# ethernet.net
KiCad netlist of a schematic drawn in Altium Designer
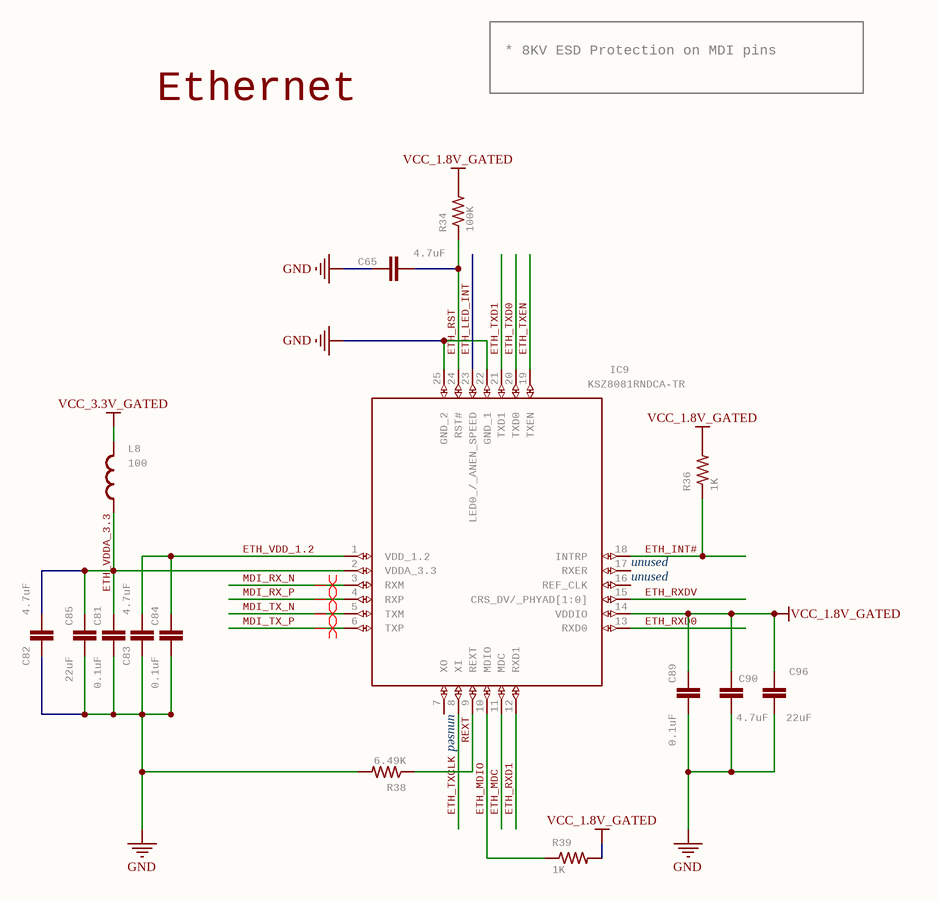
[diagram p0: ethernet.SchDoc]

(export (version "E")
  (design (tool "Eeschema 10.0.6"))
  (components
    (comp (ref "C65")
      (value "4.7uF")
      (footprint "0402-CAP")
      (description "CapacitorStandard 0603 ceramic capacitor, and 0.1\" leaded capacitor.")
      (fields (field (name "MPN") "JMK105BBJ475MV-F") (field (name "LIBRARYNAME") "sfe"))
      (libsource (lib "") (part "CAP0402-CAP_1"))
    )
    (comp (ref "C81")
      (value "0.1uF")
      (footprint "0402-CAP")
      (description "CAPACITOR, European symbol")
      (fields (field (name "MPN") "C0402C104Z4VAC"))
      (libsource (lib "openmv-ae3") (part "C-EUC0201"))
    )
    (comp (ref "C82")
      (value "4.7uF")
      (footprint "0402-CAP")
      (description "CapacitorStandard 0603 ceramic capacitor, and 0.1\" leaded capacitor.")
      (fields (field (name "MPN") "JMK105BBJ475MV-F") (field (name "LIBRARYNAME") "sfe"))
      (libsource (lib "openmv-ae3") (part "CAP0402-CAP"))
    )
    (comp (ref "C83")
      (value "4.7uF")
      (footprint "0402-CAP")
      (description "CapacitorStandard 0603 ceramic capacitor, and 0.1\" leaded capacitor.")
      (fields (field (name "MPN") "JMK105BBJ475MV-F") (field (name "LIBRARYNAME") "sfe"))
      (libsource (lib "openmv-ae3") (part "CAP0402-CAP"))
    )
    (comp (ref "C84")
      (value "0.1uF")
      (footprint "0402-CAP")
      (description "CAPACITOR, European symbol")
      (fields (field (name "MPN") "C0402C104Z4VAC"))
      (libsource (lib "openmv-ae3") (part "C-EUC0201"))
    )
    (comp (ref "C85")
      (value "22uF")
      (footprint "0805")
      (fields (field (name "MPN") "CL21A226MQQNNNE"))
      (libsource (lib "openmv-ae3") (part "22UF-0805-6.3V-20%"))
    )
    (comp (ref "C89")
      (value "0.1uF")
      (footprint "0402-CAP")
      (description "CAPACITOR, European symbol")
      (fields (field (name "MPN") "C0402C104Z4VAC"))
      (libsource (lib "openmv-ae3") (part "C-EUC0201"))
    )
    (comp (ref "C90")
      (value "4.7uF")
      (footprint "0402-CAP")
      (description "CapacitorStandard 0603 ceramic capacitor, and 0.1\" leaded capacitor.")
      (fields (field (name "MPN") "JMK105BBJ475MV-F") (field (name "LIBRARYNAME") "sfe"))
      (libsource (lib "openmv-ae3") (part "CAP0402-CAP"))
    )
    (comp (ref "C96")
      (value "22uF")
      (footprint "0805")
      (fields (field (name "MPN") "CL21A226MQQNNNE"))
      (libsource (lib "openmv-ae3") (part "22UF-0805-6.3V-20%"))
    )
    (comp (ref "IC9")
      (value "KSZ8081RNDCA-TR")
      (footprint "QFN50P400X400X90-25N")
      (description "Ethernet ICs 10/100 BASE-TX Physical Layer Transceiver   Source:  Datasheet")
      (fields (field (name "MOUSER_PART_NUMBER") "998-KSZ8081RNDCATR"))
      (libsource (lib "openmv-ae3") (part "KSZ8081RNDCA-TR"))
    )
    (comp (ref "L8")
      (value "100")
      (footprint "C0402")
      (fields (field (name "MPN") "MFBM1V1005-101-R") (field (name "LIBRARYNAME") "sfe"))
      (libsource (lib "openmv-ae3") (part "INDUCTOR0402"))
    )
    (comp (ref "R34")
      (value "100K")
      (footprint "0402-RES")
      (description "ResistorBasic schematic elements and footprints for 0603, 1206, and PTH resistors.")
      (fields (field (name "MPN") "AC0402FR-07100KL") (field (name "LIBRARYNAME") "sfe"))
      (libsource (lib "openmv-ae3") (part "RESISTOR0402-RES"))
    )
    (comp (ref "R36")
      (value "1K")
      (footprint "0402-RES")
      (description "ResistorBasic schematic elements and footprints for 0603, 1206, and PTH resistors.")
      (fields (field (name "MPN") "CRCW04021K00FKEDC") (field (name "LIBRARYNAME") "sfe"))
      (libsource (lib "openmv-ae3") (part "RESISTOR0402-RES"))
    )
    (comp (ref "R38")
      (value "6.49K")
      (footprint "0402-RES")
      (description "ResistorBasic schematic elements and footprints for 0603, 1206, and PTH resistors.")
      (fields (field (name "MPN") "CR0402-FX-6491GLF") (field (name "LIBRARYNAME") "sfe"))
      (libsource (lib "openmv-ae3") (part "RESISTOR0402-RES"))
    )
    (comp (ref "R39")
      (value "1K")
      (footprint "0402-RES")
      (description "ResistorBasic schematic elements and footprints for 0603, 1206, and PTH resistors.")
      (fields (field (name "MPN") "CRCW04021K00FKEDC") (field (name "LIBRARYNAME") "sfe"))
      (libsource (lib "openmv-ae3") (part "RESISTOR0402-RES"))
    )
  )
  (nets
    (net (code "1") (name "/ETH_INT#") (class "Default")
      (node (ref "IC9") (pin "18") (pinfunction "INTRP_18") (pintype "bidirectional"))
      (node (ref "R36") (pin "1") (pinfunction "1_1") (pintype "passive"))
    )
    (net (code "2") (name "/ETH_LED_INT") (class "Default")
      (node (ref "IC9") (pin "23") (pinfunction "LED0_/_ANEN_SPEED_23") (pintype "bidirectional"))
    )
    (net (code "3") (name "/ETH_MDC") (class "Default")
      (node (ref "IC9") (pin "11") (pinfunction "MDC_11") (pintype "bidirectional"))
    )
    (net (code "4") (name "/ETH_MDIO") (class "Default")
      (node (ref "IC9") (pin "10") (pinfunction "MDIO_10") (pintype "bidirectional"))
      (node (ref "R39") (pin "1") (pinfunction "1_1") (pintype "passive"))
    )
    (net (code "5") (name "/ETH_RST") (class "Default")
      (node (ref "C65") (pin "2") (pinfunction "2_2") (pintype "passive"))
      (node (ref "IC9") (pin "24") (pinfunction "RST#_24") (pintype "bidirectional"))
      (node (ref "R34") (pin "1") (pinfunction "1_1") (pintype "passive"))
    )
    (net (code "6") (name "/ETH_RXD0") (class "Default")
      (node (ref "IC9") (pin "13") (pinfunction "RXD0_13") (pintype "bidirectional"))
    )
    (net (code "7") (name "/ETH_RXD1") (class "Default")
      (node (ref "IC9") (pin "12") (pinfunction "RXD1_12") (pintype "bidirectional"))
    )
    (net (code "8") (name "/ETH_RXDV") (class "Default")
      (node (ref "IC9") (pin "15") (pinfunction "CRS_DV/_PHYAD[1:0]_15") (pintype "bidirectional"))
    )
    (net (code "9") (name "/ETH_TXCLK") (class "Default")
      (node (ref "IC9") (pin "8") (pinfunction "XI_8") (pintype "bidirectional"))
    )
    (net (code "10") (name "/ETH_TXD0") (class "Default")
      (node (ref "IC9") (pin "20") (pinfunction "TXD0_20") (pintype "bidirectional"))
    )
    (net (code "11") (name "/ETH_TXD1") (class "Default")
      (node (ref "IC9") (pin "21") (pinfunction "TXD1_21") (pintype "bidirectional"))
    )
    (net (code "12") (name "/ETH_TXEN") (class "Default")
      (node (ref "IC9") (pin "19") (pinfunction "TXEN_19") (pintype "bidirectional"))
    )
    (net (code "13") (name "/ETH_VDDA_3.3") (class "Default")
      (node (ref "C81") (pin "1") (pinfunction "1_1") (pintype "passive"))
      (node (ref "C82") (pin "2") (pinfunction "2_2") (pintype "passive"))
      (node (ref "C85") (pin "1") (pinfunction "1_1") (pintype "passive"))
      (node (ref "IC9") (pin "2") (pinfunction "VDDA_3.3_2") (pintype "bidirectional"))
      (node (ref "L8") (pin "1") (pinfunction "1_1") (pintype "passive"))
    )
    (net (code "14") (name "/ETH_VDD_1.2") (class "Default")
      (node (ref "C83") (pin "2") (pinfunction "2_2") (pintype "passive"))
      (node (ref "C84") (pin "1") (pinfunction "1_1") (pintype "passive"))
      (node (ref "IC9") (pin "1") (pinfunction "VDD_1.2_1") (pintype "bidirectional"))
    )
    (net (code "15") (name "/MDI_RX_N") (class "Default")
      (node (ref "IC9") (pin "3") (pinfunction "RXM_3") (pintype "bidirectional"))
    )
    (net (code "16") (name "/MDI_RX_P") (class "Default")
      (node (ref "IC9") (pin "4") (pinfunction "RXP_4") (pintype "bidirectional"))
    )
    (net (code "17") (name "/MDI_TX_N") (class "Default")
      (node (ref "IC9") (pin "5") (pinfunction "TXM_5") (pintype "bidirectional"))
    )
    (net (code "18") (name "/MDI_TX_P") (class "Default")
      (node (ref "IC9") (pin "6") (pinfunction "TXP_6") (pintype "bidirectional"))
    )
    (net (code "19") (name "/REXT") (class "Default")
      (node (ref "IC9") (pin "9") (pinfunction "REXT_9") (pintype "bidirectional"))
      (node (ref "R38") (pin "1") (pinfunction "1_1") (pintype "passive"))
    )
    (net (code "20") (name "GND") (class "Default")
      (node (ref "C65") (pin "1") (pinfunction "1_1") (pintype "passive"))
      (node (ref "C81") (pin "2") (pinfunction "2_2") (pintype "passive"))
      (node (ref "C82") (pin "1") (pinfunction "1_1") (pintype "passive"))
      (node (ref "C83") (pin "1") (pinfunction "1_1") (pintype "passive"))
      (node (ref "C84") (pin "2") (pinfunction "2_2") (pintype "passive"))
      (node (ref "C85") (pin "2") (pinfunction "2_2") (pintype "passive"))
      (node (ref "C89") (pin "2") (pinfunction "2_2") (pintype "passive"))
      (node (ref "C90") (pin "1") (pinfunction "1_1") (pintype "passive"))
      (node (ref "C96") (pin "2") (pinfunction "2_2") (pintype "passive"))
      (node (ref "IC9") (pin "22") (pinfunction "GND_1_22") (pintype "bidirectional"))
      (node (ref "IC9") (pin "25") (pinfunction "GND_2_25") (pintype "bidirectional"))
      (node (ref "R38") (pin "2") (pinfunction "2_2") (pintype "passive"))
    )
    (net (code "21") (name "VCC_1.8V_GATED") (class "Default")
      (node (ref "C89") (pin "1") (pinfunction "1_1") (pintype "passive"))
      (node (ref "C90") (pin "2") (pinfunction "2_2") (pintype "passive"))
      (node (ref "C96") (pin "1") (pinfunction "1_1") (pintype "passive"))
      (node (ref "IC9") (pin "14") (pinfunction "VDDIO_14") (pintype "bidirectional"))
      (node (ref "R34") (pin "2") (pinfunction "2_2") (pintype "passive"))
      (node (ref "R36") (pin "2") (pinfunction "2_2") (pintype "passive"))
      (node (ref "R39") (pin "2") (pinfunction "2_2") (pintype "passive"))
    )
    (net (code "22") (name "VCC_3.3V_GATED") (class "Default")
      (node (ref "L8") (pin "2") (pinfunction "2_2") (pintype "passive"))
    )
    (net (code "23") (name "unconnected-(IC9-REF_CLK-Pad16)") (class "Default")
      (node (ref "IC9") (pin "16") (pinfunction "REF_CLK_16") (pintype "bidirectional"))
    )
    (net (code "24") (name "unconnected-(IC9-RXER-Pad17)") (class "Default")
      (node (ref "IC9") (pin "17") (pinfunction "RXER_17") (pintype "bidirectional"))
    )
    (net (code "25") (name "unconnected-(IC9-XO-Pad7)") (class "Default")
      (node (ref "IC9") (pin "7") (pinfunction "XO_7") (pintype "bidirectional"))
    )
  )
)
